# luci2_device_revB.net
KiCad netlist of a schematic drawn in EAGLE
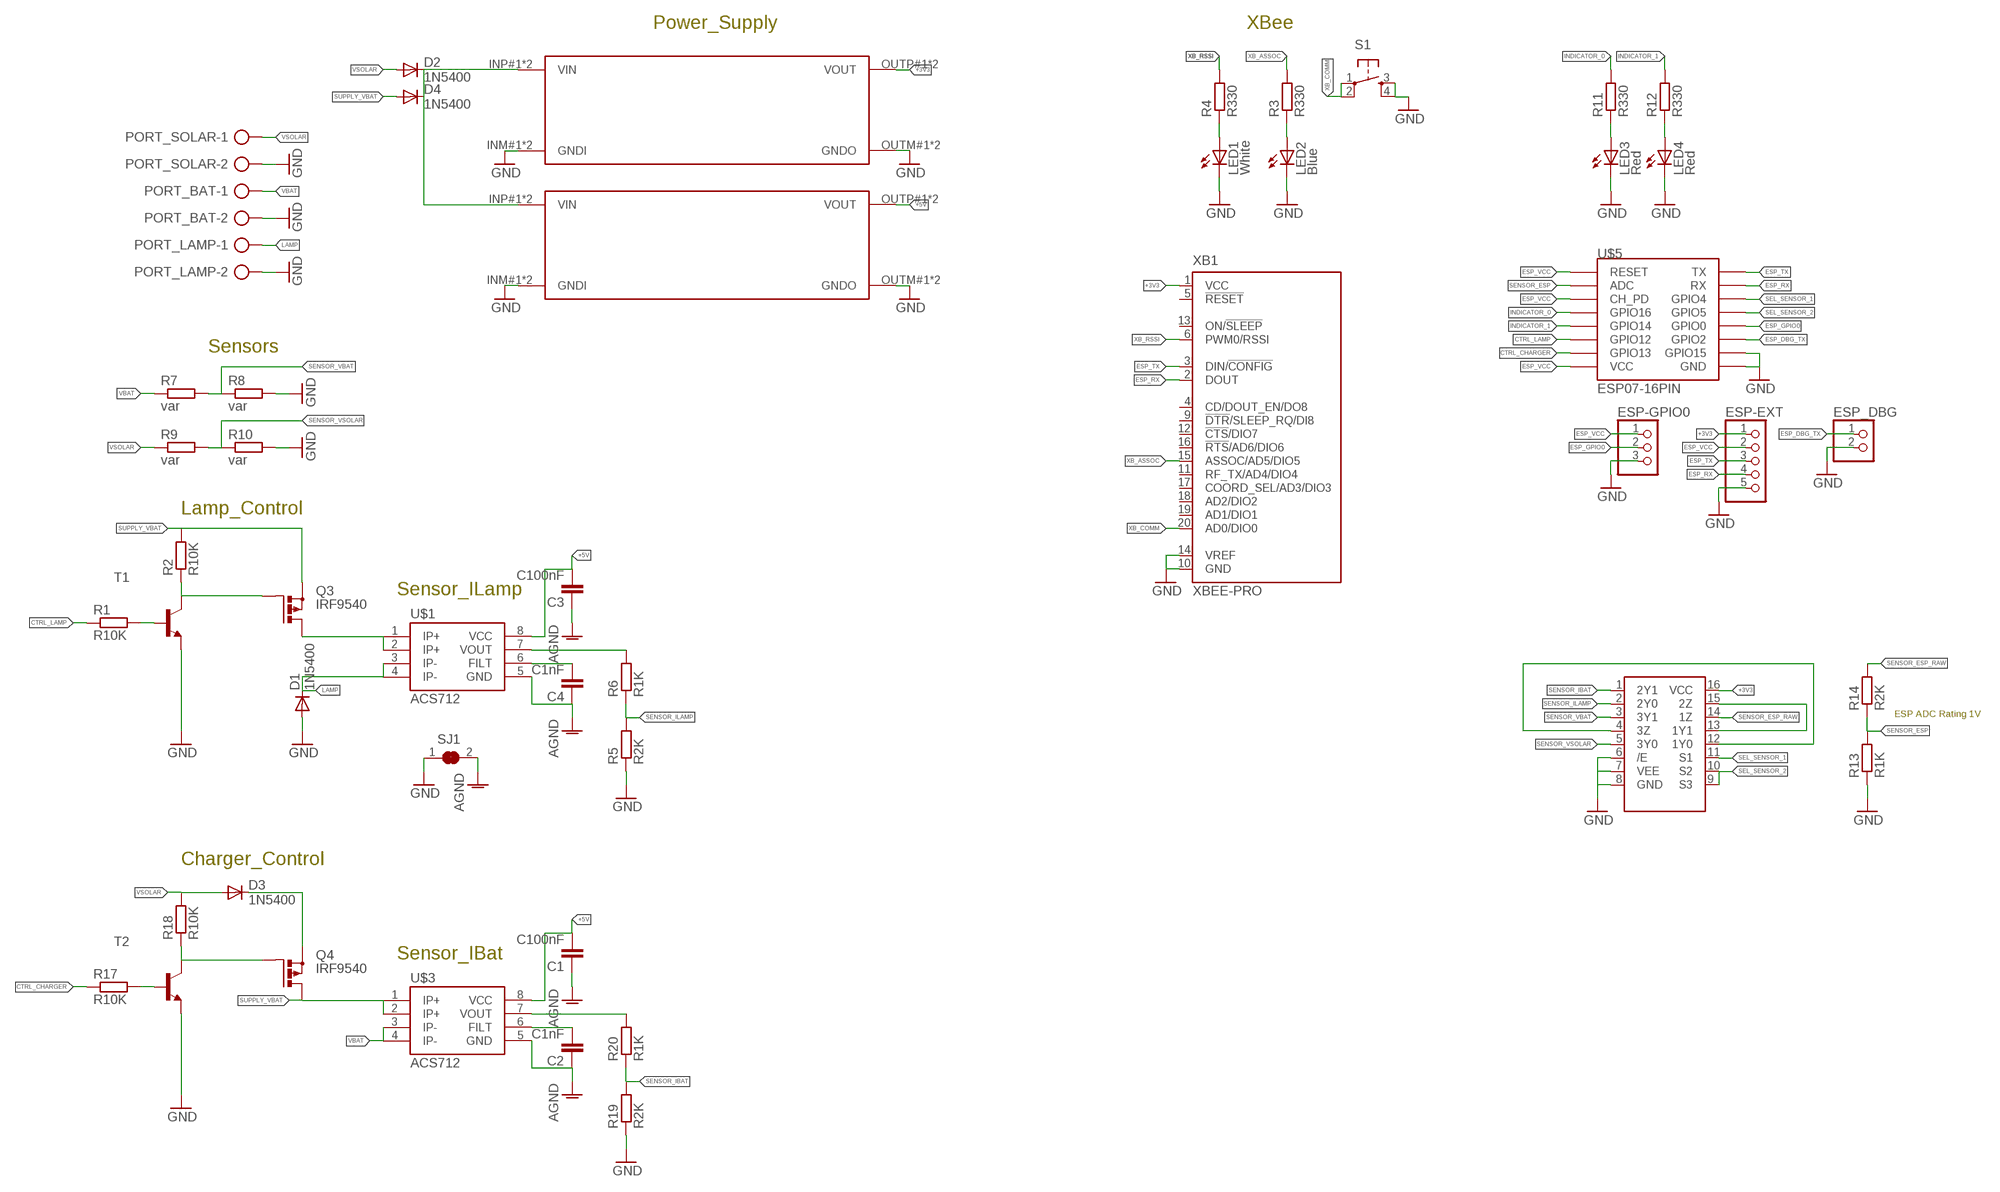
[diagram p0: schematic, sheet 1]

(export (version "E")
  (design (tool "Eeschema 10.0.6"))
  (components
    (comp (ref "C1")
      (value "C100nF")
      (footprint "eagle-import:C0805")
      (libsource (lib "eagle-import") (part "C-EUC0805"))
    )
    (comp (ref "C2")
      (value "C1nF")
      (footprint "eagle-import:C0805")
      (libsource (lib "eagle-import") (part "C-EUC0805"))
    )
    (comp (ref "C3")
      (value "C100nF")
      (footprint "eagle-import:C0805")
      (libsource (lib "eagle-import") (part "C-EUC0805"))
    )
    (comp (ref "C4")
      (value "C1nF")
      (footprint "eagle-import:C0805")
      (libsource (lib "eagle-import") (part "C-EUC0805"))
    )
    (comp (ref "D1")
      (value "1N5400")
      (footprint "eagle-import:DO201-15")
      (libsource (lib "eagle-import") (part "1N5400"))
    )
    (comp (ref "D2")
      (value "1N5400")
      (footprint "eagle-import:DO201-15")
      (libsource (lib "eagle-import") (part "1N5400"))
    )
    (comp (ref "D3")
      (value "1N5400")
      (footprint "eagle-import:DO201-15")
      (libsource (lib "eagle-import") (part "1N5400"))
    )
    (comp (ref "D4")
      (value "1N5400")
      (footprint "eagle-import:DO201-15")
      (libsource (lib "eagle-import") (part "1N5400"))
    )
    (comp (ref "ESP-EXT")
      (value "HEADER-1X5ROUND")
      (footprint "eagle-import:1X05_ROUND")
      (libsource (lib "eagle-import") (part "HEADER-1X5ROUND"))
    )
    (comp (ref "ESP-GPIO0")
      (value "HEADER-1X3ROUND")
      (footprint "eagle-import:1X03_ROUND")
      (libsource (lib "eagle-import") (part "HEADER-1X3ROUND"))
    )
    (comp (ref "ESP_DBG")
      (value "HEADER-1X2ROUND")
      (footprint "eagle-import:1X02_ROUND")
      (libsource (lib "eagle-import") (part "HEADER-1X2ROUND"))
    )
    (comp (ref "LED1")
      (value "White")
      (footprint "eagle-import:CHIPLED_0805")
      (libsource (lib "eagle-import") (part "LEDCHIPLED_0805"))
    )
    (comp (ref "LED2")
      (value "Blue")
      (footprint "eagle-import:CHIPLED_0805")
      (libsource (lib "eagle-import") (part "LEDCHIPLED_0805"))
    )
    (comp (ref "LED3")
      (value "Red")
      (footprint "eagle-import:CHIPLED_0805")
      (libsource (lib "eagle-import") (part "LEDCHIPLED_0805"))
    )
    (comp (ref "LED4")
      (value "Red")
      (footprint "eagle-import:CHIPLED_0805")
      (libsource (lib "eagle-import") (part "LEDCHIPLED_0805"))
    )
    (comp (ref "PORT_BAT")
      (value "AK300/2")
      (footprint "eagle-import:AK300_2")
      (libsource (lib "eagle-import") (part "AK300/2"))
    )
    (comp (ref "PORT_LAMP")
      (value "AK300/2")
      (footprint "eagle-import:AK300_2")
      (fields (field (name "OC_FARNELL") "unknown") (field (name "OC_NEWARK") "unknown"))
      (libsource (lib "eagle-import") (part "AK300/2"))
    )
    (comp (ref "PORT_SOLAR")
      (value "AK300/2")
      (footprint "eagle-import:AK300_2")
      (libsource (lib "eagle-import") (part "AK300/2"))
    )
    (comp (ref "Q3")
      (value "IRF9540")
      (footprint "eagle-import:TO220BV")
      (libsource (lib "eagle-import") (part "PMOSFET_PTO220BV"))
    )
    (comp (ref "Q4")
      (value "IRF9540")
      (footprint "eagle-import:TO220BV")
      (libsource (lib "eagle-import") (part "PMOSFET_PTO220BV"))
    )
    (comp (ref "R1")
      (value "R10K")
      (footprint "eagle-import:M0805")
      (libsource (lib "eagle-import") (part "R-EU_M0805"))
    )
    (comp (ref "R2")
      (value "R10K")
      (footprint "eagle-import:M0805")
      (libsource (lib "eagle-import") (part "R-EU_M0805"))
    )
    (comp (ref "R3")
      (value "R330")
      (footprint "eagle-import:M0805")
      (libsource (lib "eagle-import") (part "R-EU_M0805"))
    )
    (comp (ref "R4")
      (value "R330")
      (footprint "eagle-import:M0805")
      (libsource (lib "eagle-import") (part "R-EU_M0805"))
    )
    (comp (ref "R5")
      (value "R2K")
      (footprint "eagle-import:M0805")
      (libsource (lib "eagle-import") (part "R-EU_M0805"))
    )
    (comp (ref "R6")
      (value "R1K")
      (footprint "eagle-import:M0805")
      (libsource (lib "eagle-import") (part "R-EU_M0805"))
    )
    (comp (ref "R7")
      (value "var")
      (footprint "eagle-import:M0805")
      (libsource (lib "eagle-import") (part "R-EU_M0805"))
    )
    (comp (ref "R8")
      (value "var")
      (footprint "eagle-import:M0805")
      (libsource (lib "eagle-import") (part "R-EU_M0805"))
    )
    (comp (ref "R9")
      (value "var")
      (footprint "eagle-import:M0805")
      (libsource (lib "eagle-import") (part "R-EU_M0805"))
    )
    (comp (ref "R10")
      (value "var")
      (footprint "eagle-import:M0805")
      (libsource (lib "eagle-import") (part "R-EU_M0805"))
    )
    (comp (ref "R11")
      (value "R330")
      (footprint "eagle-import:M0805")
      (libsource (lib "eagle-import") (part "R-EU_M0805"))
    )
    (comp (ref "R12")
      (value "R330")
      (footprint "eagle-import:M0805")
      (libsource (lib "eagle-import") (part "R-EU_M0805"))
    )
    (comp (ref "R13")
      (value "R1K")
      (footprint "eagle-import:M0805")
      (libsource (lib "eagle-import") (part "R-EU_M0805"))
    )
    (comp (ref "R14")
      (value "R2K")
      (footprint "eagle-import:M0805")
      (libsource (lib "eagle-import") (part "R-EU_M0805"))
    )
    (comp (ref "R17")
      (value "R10K")
      (footprint "eagle-import:M0805")
      (libsource (lib "eagle-import") (part "R-EU_M0805"))
    )
    (comp (ref "R18")
      (value "R10K")
      (footprint "eagle-import:M0805")
      (libsource (lib "eagle-import") (part "R-EU_M0805"))
    )
    (comp (ref "R19")
      (value "R2K")
      (footprint "eagle-import:M0805")
      (libsource (lib "eagle-import") (part "R-EU_M0805"))
    )
    (comp (ref "R20")
      (value "R1K")
      (footprint "eagle-import:M0805")
      (libsource (lib "eagle-import") (part "R-EU_M0805"))
    )
    (comp (ref "S1")
      (value "TAC_SWITCHPTH")
      (footprint "eagle-import:TACTILE-PTH")
      (libsource (lib "eagle-import") (part "TAC_SWITCHPTH"))
    )
    (comp (ref "SJ1")
      (value "SOLDERJUMPER_CLOSED")
      (footprint "eagle-import:SOLDERJUMPER_CLOSEDWIRE")
      (libsource (lib "eagle-import") (part "SOLDERJUMPER_CLOSED"))
    )
    (comp (ref "T1")
      (value "MMBT2222ALT1-NPN-SOT23-BEC")
      (footprint "eagle-import:SOT23-BEC")
      (libsource (lib "eagle-import") (part "-NPN-SOT23-BECMMBT2222ALT1"))
    )
    (comp (ref "T2")
      (value "MMBT2222ALT1-NPN-SOT23-BEC")
      (footprint "eagle-import:SOT23-BEC")
      (libsource (lib "eagle-import") (part "-NPN-SOT23-BECMMBT2222ALT1"))
    )
    (comp (ref "U$1")
      (value "ACS712")
      (footprint "eagle-import:SO08")
      (libsource (lib "eagle-import") (part "ACS712"))
    )
    (comp (ref "U$2")
      (value "DCDCMODULE_SMALL")
      (footprint "eagle-import:DCDCMODULE-SMALL")
      (libsource (lib "eagle-import") (part "DCDCMODULE_SMALL"))
    )
    (comp (ref "U$3")
      (value "ACS712")
      (footprint "eagle-import:SO08")
      (libsource (lib "eagle-import") (part "ACS712"))
    )
    (comp (ref "U$4")
      (value "DCDCMODULE_SMALL")
      (footprint "eagle-import:DCDCMODULE-SMALL")
      (libsource (lib "eagle-import") (part "DCDCMODULE_SMALL"))
    )
    (comp (ref "U$5")
      (value "ESP07-16PIN")
      (footprint "eagle-import:ESP07-16PIN")
      (libsource (lib "eagle-import") (part "ESP07-16PIN"))
    )
    (comp (ref "U$6")
      (value "74HC4053D")
      (footprint "eagle-import:SO16")
      (libsource (lib "eagle-import") (part "74HC4053D"))
    )
    (comp (ref "XB1")
      (value "XBEE-PRO")
      (footprint "eagle-import:XBEE-PRO")
      (libsource (lib "eagle-import") (part "XBEE-PRO"))
    )
  )
  (nets
    (net (code "1") (name "+3V3") (class "Default")
      (node (ref "ESP-EXT") (pin "1") (pinfunction "1_1") (pintype "passive"))
      (node (ref "U$4") (pin "OUTP#1") (pinfunction "VOUT_OUTP#1") (pintype "bidirectional"))
      (node (ref "U$4") (pin "OUTP#2") (pinfunction "VOUT_OUTP#2") (pintype "bidirectional"))
      (node (ref "U$6") (pin "16") (pinfunction "VCC_16") (pintype "bidirectional"))
      (node (ref "XB1") (pin "1") (pinfunction "VCC_1") (pintype "power_in"))
    )
    (net (code "2") (name "+5V") (class "Default")
      (node (ref "C1") (pin "2") (pinfunction "2_2") (pintype "passive"))
      (node (ref "C3") (pin "2") (pinfunction "2_2") (pintype "passive"))
      (node (ref "U$1") (pin "8") (pinfunction "VCC_8") (pintype "bidirectional"))
      (node (ref "U$2") (pin "OUTP#1") (pinfunction "VOUT_OUTP#1") (pintype "bidirectional"))
      (node (ref "U$2") (pin "OUTP#2") (pinfunction "VOUT_OUTP#2") (pintype "bidirectional"))
      (node (ref "U$3") (pin "8") (pinfunction "VCC_8") (pintype "bidirectional"))
    )
    (net (code "3") (name "AGND") (class "Default")
      (node (ref "C1") (pin "1") (pinfunction "1_1") (pintype "passive"))
      (node (ref "C2") (pin "1") (pinfunction "1_1") (pintype "passive"))
      (node (ref "C3") (pin "1") (pinfunction "1_1") (pintype "passive"))
      (node (ref "C4") (pin "1") (pinfunction "1_1") (pintype "passive"))
      (node (ref "SJ1") (pin "2") (pinfunction "2_2") (pintype "passive"))
      (node (ref "U$1") (pin "5") (pinfunction "GND_5") (pintype "bidirectional"))
      (node (ref "U$3") (pin "5") (pinfunction "GND_5") (pintype "bidirectional"))
    )
    (net (code "4") (name "CTRL_CHARGER") (class "Default")
      (node (ref "R17") (pin "1") (pinfunction "1_1") (pintype "passive"))
      (node (ref "U$5") (pin "GPIO13") (pinfunction "GPIO13_GPIO13") (pintype "bidirectional"))
    )
    (net (code "5") (name "CTRL_LAMP") (class "Default")
      (node (ref "R1") (pin "1") (pinfunction "1_1") (pintype "passive"))
      (node (ref "U$5") (pin "GPIO12") (pinfunction "GPIO12_GPIO12") (pintype "bidirectional"))
    )
    (net (code "6") (name "ESP_DBG_TX") (class "Default")
      (node (ref "ESP_DBG") (pin "1") (pinfunction "1_1") (pintype "passive"))
      (node (ref "U$5") (pin "GPIO2") (pinfunction "GPIO2_GPIO2") (pintype "bidirectional"))
    )
    (net (code "7") (name "ESP_GPIO0") (class "Default")
      (node (ref "ESP-GPIO0") (pin "2") (pinfunction "2_2") (pintype "passive"))
      (node (ref "U$5") (pin "GPIO0") (pinfunction "GPIO0_GPIO0") (pintype "bidirectional"))
    )
    (net (code "8") (name "ESP_RX") (class "Default")
      (node (ref "ESP-EXT") (pin "4") (pinfunction "4_4") (pintype "passive"))
      (node (ref "U$5") (pin "RX") (pinfunction "RX_RX") (pintype "bidirectional"))
      (node (ref "XB1") (pin "2") (pinfunction "DOUT_2") (pintype "output"))
    )
    (net (code "9") (name "ESP_TX") (class "Default")
      (node (ref "ESP-EXT") (pin "3") (pinfunction "3_3") (pintype "passive"))
      (node (ref "U$5") (pin "TX") (pinfunction "TX_TX") (pintype "bidirectional"))
      (node (ref "XB1") (pin "3") (pinfunction "DIN/~{CONFIG}_3") (pintype "input"))
    )
    (net (code "10") (name "ESP_VCC") (class "Default")
      (node (ref "ESP-EXT") (pin "2") (pinfunction "2_2") (pintype "passive"))
      (node (ref "ESP-GPIO0") (pin "1") (pinfunction "1_1") (pintype "passive"))
      (node (ref "U$5") (pin "CH_PD") (pinfunction "CH_PD_CH_PD") (pintype "bidirectional"))
      (node (ref "U$5") (pin "REST") (pinfunction "RESET_REST") (pintype "bidirectional"))
      (node (ref "U$5") (pin "VCC") (pinfunction "VCC_VCC") (pintype "bidirectional"))
    )
    (net (code "11") (name "GND") (class "Default")
      (node (ref "D1") (pin "A") (pinfunction "A_A") (pintype "passive"))
      (node (ref "ESP-EXT") (pin "5") (pinfunction "5_5") (pintype "passive"))
      (node (ref "ESP-GPIO0") (pin "3") (pinfunction "3_3") (pintype "passive"))
      (node (ref "ESP_DBG") (pin "2") (pinfunction "2_2") (pintype "passive"))
      (node (ref "LED1") (pin "C") (pinfunction "C_C") (pintype "passive"))
      (node (ref "LED2") (pin "C") (pinfunction "C_C") (pintype "passive"))
      (node (ref "LED3") (pin "C") (pinfunction "C_C") (pintype "passive"))
      (node (ref "LED4") (pin "C") (pinfunction "C_C") (pintype "passive"))
      (node (ref "PORT_BAT") (pin "2") (pinfunction "KL_2") (pintype "passive"))
      (node (ref "PORT_LAMP") (pin "2") (pinfunction "KL_2") (pintype "passive"))
      (node (ref "PORT_SOLAR") (pin "2") (pinfunction "KL_2") (pintype "passive"))
      (node (ref "R10") (pin "2") (pinfunction "2_2") (pintype "passive"))
      (node (ref "R13") (pin "1") (pinfunction "1_1") (pintype "passive"))
      (node (ref "R19") (pin "1") (pinfunction "1_1") (pintype "passive"))
      (node (ref "R5") (pin "1") (pinfunction "1_1") (pintype "passive"))
      (node (ref "R8") (pin "2") (pinfunction "2_2") (pintype "passive"))
      (node (ref "S1") (pin "3") (pinfunction "3_3") (pintype "passive"))
      (node (ref "S1") (pin "4") (pinfunction "4_4") (pintype "passive"))
      (node (ref "SJ1") (pin "1") (pinfunction "1_1") (pintype "passive"))
      (node (ref "T1") (pin "E") (pinfunction "E_E") (pintype "passive"))
      (node (ref "T2") (pin "E") (pinfunction "E_E") (pintype "passive"))
      (node (ref "U$2") (pin "INM#1") (pinfunction "GNDI_INM#1") (pintype "bidirectional"))
      (node (ref "U$2") (pin "INM#2") (pinfunction "GNDI_INM#2") (pintype "bidirectional"))
      (node (ref "U$2") (pin "OUTM#1") (pinfunction "GNDO_OUTM#1") (pintype "bidirectional"))
      (node (ref "U$2") (pin "OUTM#2") (pinfunction "GNDO_OUTM#2") (pintype "bidirectional"))
      (node (ref "U$4") (pin "INM#1") (pinfunction "GNDI_INM#1") (pintype "bidirectional"))
      (node (ref "U$4") (pin "INM#2") (pinfunction "GNDI_INM#2") (pintype "bidirectional"))
      (node (ref "U$4") (pin "OUTM#1") (pinfunction "GNDO_OUTM#1") (pintype "bidirectional"))
      (node (ref "U$4") (pin "OUTM#2") (pinfunction "GNDO_OUTM#2") (pintype "bidirectional"))
      (node (ref "U$5") (pin "GND") (pinfunction "GND_GND") (pintype "bidirectional"))
      (node (ref "U$5") (pin "GPIO15") (pinfunction "GPIO15_GPIO15") (pintype "bidirectional"))
      (node (ref "U$6") (pin "6") (pinfunction "/E_6") (pintype "bidirectional"))
      (node (ref "U$6") (pin "7") (pinfunction "VEE_7") (pintype "bidirectional"))
      (node (ref "U$6") (pin "8") (pinfunction "GND_8") (pintype "bidirectional"))
      (node (ref "XB1") (pin "10") (pinfunction "GND_10") (pintype "power_in"))
      (node (ref "XB1") (pin "14") (pinfunction "VREF_14") (pintype "input"))
    )
    (net (code "12") (name "INDICATOR_0") (class "Default")
      (node (ref "R11") (pin "2") (pinfunction "2_2") (pintype "passive"))
      (node (ref "U$5") (pin "GPIO16") (pinfunction "GPIO16_GPIO16") (pintype "bidirectional"))
    )
    (net (code "13") (name "INDICATOR_1") (class "Default")
      (node (ref "R12") (pin "2") (pinfunction "2_2") (pintype "passive"))
      (node (ref "U$5") (pin "GPIO14") (pinfunction "GPIO14_GPIO14") (pintype "bidirectional"))
    )
    (net (code "14") (name "LAMP") (class "Default")
      (node (ref "D1") (pin "C") (pinfunction "C_C") (pintype "passive"))
      (node (ref "PORT_LAMP") (pin "1") (pinfunction "KL_1") (pintype "passive"))
      (node (ref "U$1") (pin "3") (pinfunction "IP-_3") (pintype "bidirectional"))
      (node (ref "U$1") (pin "4") (pinfunction "IP-_4") (pintype "bidirectional"))
    )
    (net (code "15") (name "Net-(D2-PadC)") (class "Default")
      (node (ref "D2") (pin "C") (pinfunction "C_C") (pintype "passive"))
      (node (ref "D4") (pin "C") (pinfunction "C_C") (pintype "passive"))
      (node (ref "U$2") (pin "INP#1") (pinfunction "VIN_INP#1") (pintype "bidirectional"))
      (node (ref "U$2") (pin "INP#2") (pinfunction "VIN_INP#2") (pintype "bidirectional"))
      (node (ref "U$4") (pin "INP#1") (pinfunction "VIN_INP#1") (pintype "bidirectional"))
      (node (ref "U$4") (pin "INP#2") (pinfunction "VIN_INP#2") (pintype "bidirectional"))
    )
    (net (code "16") (name "Net-(D3-PadC)") (class "Default")
      (node (ref "D3") (pin "C") (pinfunction "C_C") (pintype "passive"))
      (node (ref "Q4") (pin "S") (pinfunction "S_S") (pintype "passive"))
    )
    (net (code "17") (name "Net-(LED1-PadA)") (class "Default")
      (node (ref "LED1") (pin "A") (pinfunction "A_A") (pintype "passive"))
      (node (ref "R4") (pin "1") (pinfunction "1_1") (pintype "passive"))
    )
    (net (code "18") (name "Net-(LED2-PadA)") (class "Default")
      (node (ref "LED2") (pin "A") (pinfunction "A_A") (pintype "passive"))
      (node (ref "R3") (pin "1") (pinfunction "1_1") (pintype "passive"))
    )
    (net (code "19") (name "Net-(LED3-PadA)") (class "Default")
      (node (ref "LED3") (pin "A") (pinfunction "A_A") (pintype "passive"))
      (node (ref "R11") (pin "1") (pinfunction "1_1") (pintype "passive"))
    )
    (net (code "20") (name "Net-(LED4-PadA)") (class "Default")
      (node (ref "LED4") (pin "A") (pinfunction "A_A") (pintype "passive"))
      (node (ref "R12") (pin "1") (pinfunction "1_1") (pintype "passive"))
    )
    (net (code "21") (name "Net-(Q3-PadD)") (class "Default")
      (node (ref "Q3") (pin "D") (pinfunction "D_D") (pintype "passive"))
      (node (ref "U$1") (pin "1") (pinfunction "IP+_1") (pintype "bidirectional"))
      (node (ref "U$1") (pin "2") (pinfunction "IP+_2") (pintype "bidirectional"))
    )
    (net (code "22") (name "Net-(Q3-PadG)") (class "Default")
      (node (ref "Q3") (pin "G") (pinfunction "G_G") (pintype "passive"))
      (node (ref "R2") (pin "1") (pinfunction "1_1") (pintype "passive"))
      (node (ref "T1") (pin "C") (pinfunction "C_C") (pintype "passive"))
    )
    (net (code "23") (name "Net-(Q4-PadG)") (class "Default")
      (node (ref "Q4") (pin "G") (pinfunction "G_G") (pintype "passive"))
      (node (ref "R18") (pin "1") (pinfunction "1_1") (pintype "passive"))
      (node (ref "T2") (pin "C") (pinfunction "C_C") (pintype "passive"))
    )
    (net (code "24") (name "Net-(R1-Pad2)") (class "Default")
      (node (ref "R1") (pin "2") (pinfunction "2_2") (pintype "passive"))
      (node (ref "T1") (pin "B") (pinfunction "B_B") (pintype "passive"))
    )
    (net (code "25") (name "Net-(R17-Pad2)") (class "Default")
      (node (ref "R17") (pin "2") (pinfunction "2_2") (pintype "passive"))
      (node (ref "T2") (pin "B") (pinfunction "B_B") (pintype "passive"))
    )
    (net (code "26") (name "Net-(U$1-FILT)") (class "Default")
      (node (ref "C4") (pin "2") (pinfunction "2_2") (pintype "passive"))
      (node (ref "U$1") (pin "6") (pinfunction "FILT_6") (pintype "bidirectional"))
    )
    (net (code "27") (name "Net-(U$1-VOUT)") (class "Default")
      (node (ref "R6") (pin "2") (pinfunction "2_2") (pintype "passive"))
      (node (ref "U$1") (pin "7") (pinfunction "VOUT_7") (pintype "bidirectional"))
    )
    (net (code "28") (name "Net-(U$3-FILT)") (class "Default")
      (node (ref "C2") (pin "2") (pinfunction "2_2") (pintype "passive"))
      (node (ref "U$3") (pin "6") (pinfunction "FILT_6") (pintype "bidirectional"))
    )
    (net (code "29") (name "Net-(U$3-VOUT)") (class "Default")
      (node (ref "R20") (pin "2") (pinfunction "2_2") (pintype "passive"))
      (node (ref "U$3") (pin "7") (pinfunction "VOUT_7") (pintype "bidirectional"))
    )
    (net (code "30") (name "Net-(U$6-1Y0)") (class "Default")
      (node (ref "U$6") (pin "12") (pinfunction "1Y0_12") (pintype "bidirectional"))
      (node (ref "U$6") (pin "4") (pinfunction "3Z_4") (pintype "bidirectional"))
    )
    (net (code "31") (name "Net-(U$6-1Y1)") (class "Default")
      (node (ref "U$6") (pin "13") (pinfunction "1Y1_13") (pintype "bidirectional"))
      (node (ref "U$6") (pin "15") (pinfunction "2Z_15") (pintype "bidirectional"))
    )
    (net (code "32") (name "SEL_SENSOR_1") (class "Default")
      (node (ref "U$5") (pin "GPIO4") (pinfunction "GPIO4_GPIO4") (pintype "bidirectional"))
      (node (ref "U$6") (pin "11") (pinfunction "S1_11") (pintype "bidirectional"))
    )
    (net (code "33") (name "SEL_SENSOR_2") (class "Default")
      (node (ref "U$5") (pin "GPIO5") (pinfunction "GPIO5_GPIO5") (pintype "bidirectional"))
      (node (ref "U$6") (pin "10") (pinfunction "S2_10") (pintype "bidirectional"))
      (node (ref "U$6") (pin "9") (pinfunction "S3_9") (pintype "bidirectional"))
    )
    (net (code "34") (name "SENSOR_ESP") (class "Default")
      (node (ref "R13") (pin "2") (pinfunction "2_2") (pintype "passive"))
      (node (ref "R14") (pin "1") (pinfunction "1_1") (pintype "passive"))
      (node (ref "U$5") (pin "ADC") (pinfunction "ADC_ADC") (pintype "bidirectional"))
    )
    (net (code "35") (name "SENSOR_ESP_RAW") (class "Default")
      (node (ref "R14") (pin "2") (pinfunction "2_2") (pintype "passive"))
      (node (ref "U$6") (pin "14") (pinfunction "1Z_14") (pintype "bidirectional"))
    )
    (net (code "36") (name "SENSOR_IBAT") (class "Default")
      (node (ref "R19") (pin "2") (pinfunction "2_2") (pintype "passive"))
      (node (ref "R20") (pin "1") (pinfunction "1_1") (pintype "passive"))
      (node (ref "U$6") (pin "1") (pinfunction "2Y1_1") (pintype "bidirectional"))
    )
    (net (code "37") (name "SENSOR_ILAMP") (class "Default")
      (node (ref "R5") (pin "2") (pinfunction "2_2") (pintype "passive"))
      (node (ref "R6") (pin "1") (pinfunction "1_1") (pintype "passive"))
      (node (ref "U$6") (pin "2") (pinfunction "2Y0_2") (pintype "bidirectional"))
    )
    (net (code "38") (name "SENSOR_VBAT") (class "Default")
      (node (ref "R7") (pin "2") (pinfunction "2_2") (pintype "passive"))
      (node (ref "R8") (pin "1") (pinfunction "1_1") (pintype "passive"))
      (node (ref "U$6") (pin "3") (pinfunction "3Y1_3") (pintype "bidirectional"))
    )
    (net (code "39") (name "SENSOR_VSOLAR") (class "Default")
      (node (ref "R10") (pin "1") (pinfunction "1_1") (pintype "passive"))
      (node (ref "R9") (pin "2") (pinfunction "2_2") (pintype "passive"))
      (node (ref "U$6") (pin "5") (pinfunction "3Y0_5") (pintype "bidirectional"))
    )
    (net (code "40") (name "SUPPLY_VBAT") (class "Default")
      (node (ref "D4") (pin "A") (pinfunction "A_A") (pintype "passive"))
      (node (ref "Q3") (pin "S") (pinfunction "S_S") (pintype "passive"))
      (node (ref "Q4") (pin "D") (pinfunction "D_D") (pintype "passive"))
      (node (ref "R2") (pin "2") (pinfunction "2_2") (pintype "passive"))
      (node (ref "U$3") (pin "1") (pinfunction "IP+_1") (pintype "bidirectional"))
      (node (ref "U$3") (pin "2") (pinfunction "IP+_2") (pintype "bidirectional"))
    )
    (net (code "41") (name "VBAT") (class "Default")
      (node (ref "PORT_BAT") (pin "1") (pinfunction "KL_1") (pintype "passive"))
      (node (ref "R7") (pin "1") (pinfunction "1_1") (pintype "passive"))
      (node (ref "U$3") (pin "3") (pinfunction "IP-_3") (pintype "bidirectional"))
      (node (ref "U$3") (pin "4") (pinfunction "IP-_4") (pintype "bidirectional"))
    )
    (net (code "42") (name "VSOLAR") (class "Default")
      (node (ref "D2") (pin "A") (pinfunction "A_A") (pintype "passive"))
      (node (ref "D3") (pin "A") (pinfunction "A_A") (pintype "passive"))
      (node (ref "PORT_SOLAR") (pin "1") (pinfunction "KL_1") (pintype "passive"))
      (node (ref "R18") (pin "2") (pinfunction "2_2") (pintype "passive"))
      (node (ref "R9") (pin "1") (pinfunction "1_1") (pintype "passive"))
    )
    (net (code "43") (name "XB_ASSOC") (class "Default")
      (node (ref "R3") (pin "2") (pinfunction "2_2") (pintype "passive"))
      (node (ref "XB1") (pin "15") (pinfunction "ASSOC/AD5/DIO5_15") (pintype "bidirectional"))
    )
    (net (code "44") (name "XB_COMM") (class "Default")
      (node (ref "S1") (pin "1") (pinfunction "1_1") (pintype "passive"))
      (node (ref "S1") (pin "2") (pinfunction "2_2") (pintype "passive"))
      (node (ref "XB1") (pin "20") (pinfunction "AD0/DIO0_20") (pintype "bidirectional"))
    )
    (net (code "45") (name "XB_RSSI") (class "Default")
      (node (ref "R4") (pin "2") (pinfunction "2_2") (pintype "passive"))
      (node (ref "XB1") (pin "6") (pinfunction "PWM0/RSSI_6") (pintype "output"))
    )
    (net (code "46") (name "unconnected-(XB1-AD1{slash}DIO1-Pad19)") (class "Default")
      (node (ref "XB1") (pin "19") (pinfunction "AD1/DIO1_19") (pintype "bidirectional"))
    )
    (net (code "47") (name "unconnected-(XB1-AD2{slash}DIO2-Pad18)") (class "Default")
      (node (ref "XB1") (pin "18") (pinfunction "AD2/DIO2_18") (pintype "bidirectional"))
    )
    (net (code "48") (name "unconnected-(XB1-CD{slash}DOUT_EN{slash}DO8-Pad4)") (class "Default")
      (node (ref "XB1") (pin "4") (pinfunction "CD/DOUT_EN/DO8_4") (pintype "output"))
    )
    (net (code "49") (name "unconnected-(XB1-COORD_SEL{slash}AD3{slash}DIO3-Pad17)") (class "Default")
      (node (ref "XB1") (pin "17") (pinfunction "COORD_SEL/AD3/DIO3_17") (pintype "bidirectional"))
    )
    (net (code "50") (name "unconnected-(XB1-ON{slash}~{SLEEP}-Pad13)") (class "Default")
      (node (ref "XB1") (pin "13") (pinfunction "ON/~{SLEEP}_13") (pintype "output"))
    )
    (net (code "51") (name "unconnected-(XB1-RF_TX{slash}AD4{slash}DIO4-Pad11)") (class "Default")
      (node (ref "XB1") (pin "11") (pinfunction "RF_TX/AD4/DIO4_11") (pintype "bidirectional"))
    )
    (net (code "52") (name "unconnected-(XB1-~{CTS}{slash}DIO7-Pad12)") (class "Default")
      (node (ref "XB1") (pin "12") (pinfunction "~{CTS}/DIO7_12") (pintype "bidirectional"))
    )
    (net (code "53") (name "unconnected-(XB1-~{DTR}{slash}SLEEP_RQ{slash}DI8-Pad9)") (class "Default")
      (node (ref "XB1") (pin "9") (pinfunction "~{DTR}/SLEEP_RQ/DI8_9") (pintype "bidirectional"))
    )
    (net (code "54") (name "unconnected-(XB1-~{RESET}-Pad5)") (class "Default")
      (node (ref "XB1") (pin "5") (pinfunction "~{RESET}_5") (pintype "input"))
    )
    (net (code "55") (name "unconnected-(XB1-~{RTS}{slash}AD6{slash}DIO6-Pad16)") (class "Default")
      (node (ref "XB1") (pin "16") (pinfunction "~{RTS}/AD6/DIO6_16") (pintype "bidirectional"))
    )
  )
)
